# SCH_CM_Mesa_7i92TH_2024-10-26.net
KiCad netlist of a schematic drawn in EasyEDA
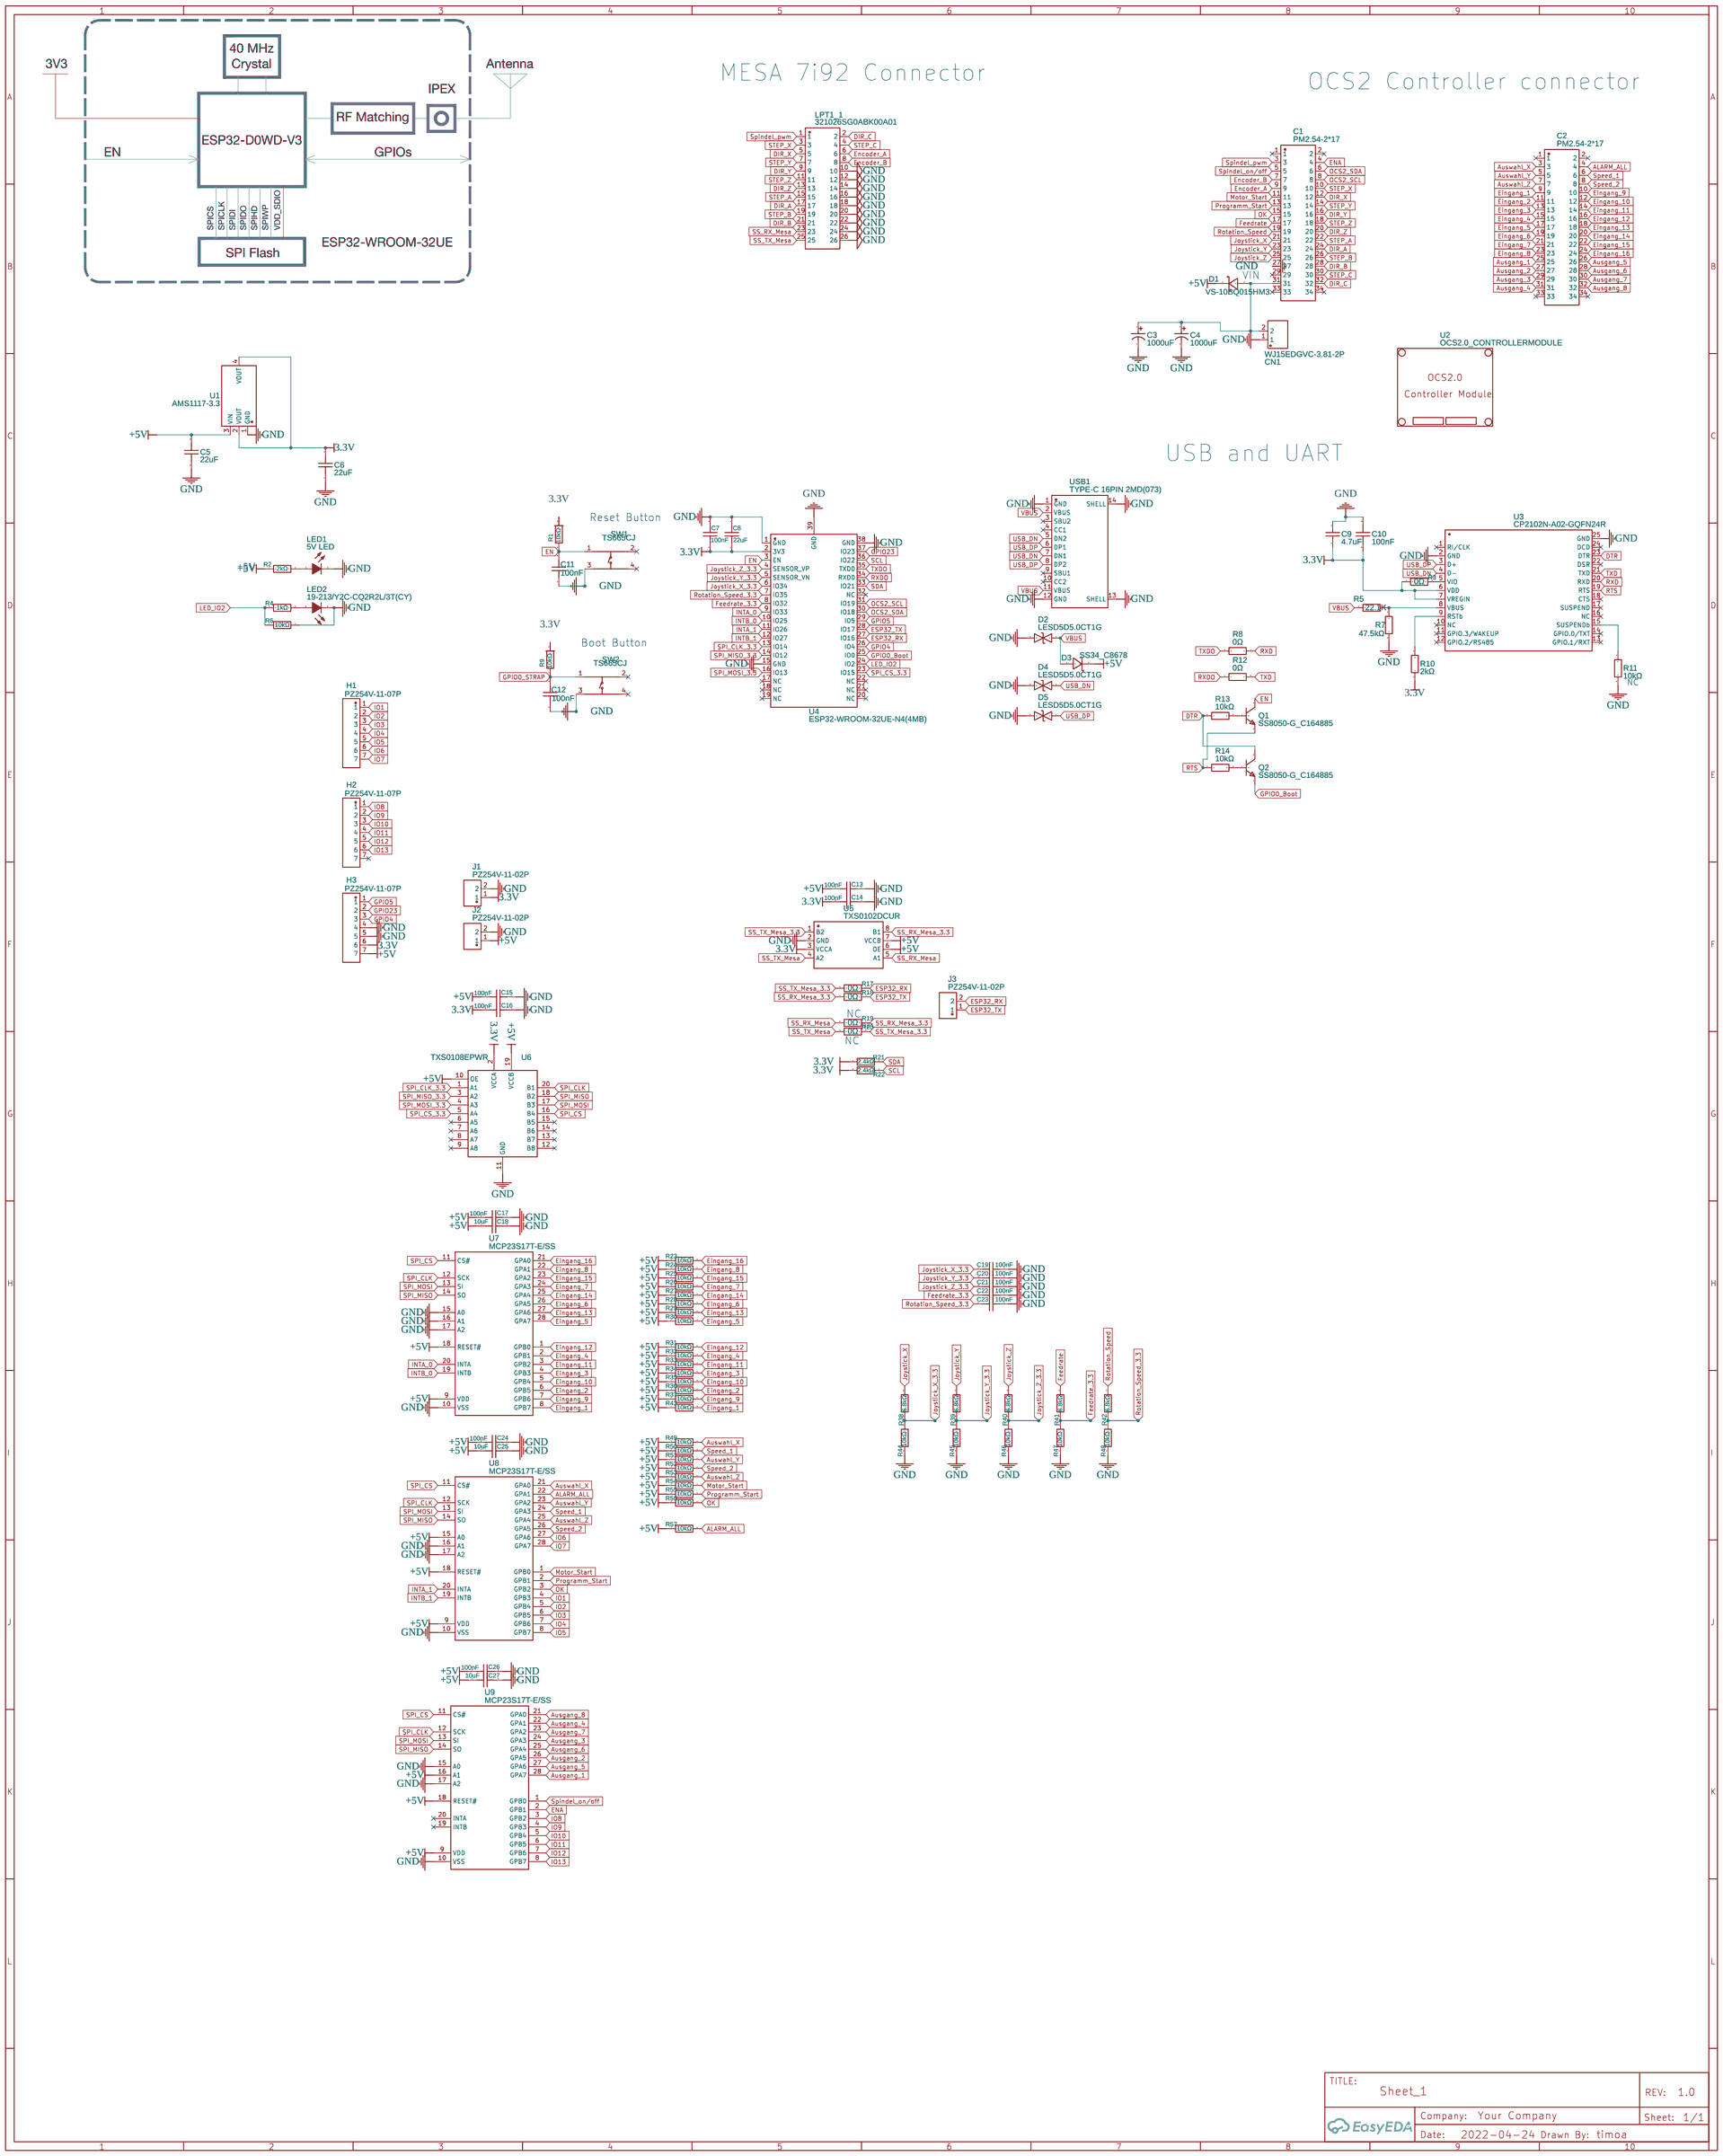
[diagram p0: schematic sheet]

(export (version "E")
  (design (tool "Eeschema 10.0.6"))
  (components
    (comp (ref "C1")
      (value "PM2.54-2*17")
      (fields (field (name "Manufacturer") "CONNFLY"))
      (libsource (lib "") (part "PM2.54-2*17"))
    )
    (comp (ref "C2")
      (value "PM2.54-2*17")
      (fields (field (name "Manufacturer") "CONNFLY"))
      (libsource (lib "") (part "PM2.54-2*17"))
    )
    (comp (ref "C3")
      (value "1000uF")
      (fields (field (name "Manufacturer Part") "RVT1C102M1010VG") (field (name "Manufacturer") "CX(承兴)"))
      (libsource (lib "") (part "UT1C102M1010VG"))
    )
    (comp (ref "C4")
      (value "1000uF")
      (fields (field (name "Manufacturer Part") "RVT1C102M1010VG") (field (name "Manufacturer") "CX(承兴)"))
      (libsource (lib "") (part "UT1C102M1010VG"))
    )
    (comp (ref "C5")
      (value "22uF")
      (fields
        (field (name "Manufacturer Part") "CC1210ZKY5V6BB226")
        (field (name "Manufacturer") "YAGEO(国巨)")
      )
      (libsource (lib "") (part "CC1210ZKY5V6BB226"))
    )
    (comp (ref "C6")
      (value "22uF")
      (fields
        (field (name "Manufacturer Part") "CC1210ZKY5V6BB226")
        (field (name "Manufacturer") "YAGEO(国巨)")
      )
      (libsource (lib "") (part "CC1210ZKY5V6BB226"))
    )
    (comp (ref "C7")
      (value "100nF")
      (fields
        (field (name "Manufacturer Part") "CC0603KRX7R9BB104")
        (field (name "Manufacturer") "YAGEO(国巨)")
      )
      (libsource (lib "") (part "CC0603KRX7R9BB104"))
    )
    (comp (ref "C8")
      (value "22uF")
      (fields
        (field (name "Manufacturer Part") "CC1210ZKY5V6BB226")
        (field (name "Manufacturer") "YAGEO(国巨)")
      )
      (libsource (lib "") (part "CC1210ZKY5V6BB226"))
    )
    (comp (ref "C9")
      (value "4.7uF")
      (fields
        (field (name "Manufacturer Part") "CL05A475MP5NRNC")
        (field (name "Manufacturer") "SAMSUNG(三星)")
      )
      (libsource (lib "") (part "CL05A475MP5NRNC"))
    )
    (comp (ref "C10")
      (value "100nF")
      (fields
        (field (name "Manufacturer Part") "CC0603KRX7R9BB104")
        (field (name "Manufacturer") "YAGEO(国巨)")
      )
      (libsource (lib "") (part "CC0603KRX7R9BB104_1"))
    )
    (comp (ref "C11")
      (value "100nF")
      (fields
        (field (name "Manufacturer Part") "CC0603KRX7R9BB104")
        (field (name "Manufacturer") "YAGEO(国巨)")
      )
      (libsource (lib "") (part "CC0603KRX7R9BB104"))
    )
    (comp (ref "C12")
      (value "100nF")
      (fields
        (field (name "Manufacturer Part") "CC0603KRX7R9BB104")
        (field (name "Manufacturer") "YAGEO(国巨)")
      )
      (libsource (lib "") (part "CC0603KRX7R9BB104"))
    )
    (comp (ref "C13")
      (value "100nF")
      (fields
        (field (name "Manufacturer Part") "CC0603KRX7R9BB104")
        (field (name "Manufacturer") "YAGEO(国巨)")
      )
      (libsource (lib "") (part "CC0603KRX7R9BB104_2"))
    )
    (comp (ref "C14")
      (value "100nF")
      (fields
        (field (name "Manufacturer Part") "CC0603KRX7R9BB104")
        (field (name "Manufacturer") "YAGEO(国巨)")
      )
      (libsource (lib "") (part "CC0603KRX7R9BB104_2"))
    )
    (comp (ref "C15")
      (value "100nF")
      (fields
        (field (name "Manufacturer Part") "CC0603KRX7R9BB104")
        (field (name "Manufacturer") "YAGEO(国巨)")
      )
      (libsource (lib "") (part "CC0603KRX7R9BB104_2"))
    )
    (comp (ref "C16")
      (value "100nF")
      (fields
        (field (name "Manufacturer Part") "CC0603KRX7R9BB104")
        (field (name "Manufacturer") "YAGEO(国巨)")
      )
      (libsource (lib "") (part "CC0603KRX7R9BB104_2"))
    )
    (comp (ref "C17")
      (value "100nF")
      (fields
        (field (name "Manufacturer Part") "CC0603KRX7R9BB104")
        (field (name "Manufacturer") "YAGEO(国巨)")
      )
      (libsource (lib "") (part "CC0603KRX7R9BB104_2"))
    )
    (comp (ref "C18")
      (value "10uF")
      (fields
        (field (name "Manufacturer Part") "CL10A106KP8NNNC")
        (field (name "Manufacturer") "SAMSUNG(三星)")
      )
      (libsource (lib "") (part "CL10A106KP8NNNC"))
    )
    (comp (ref "C19")
      (value "100nF")
      (fields
        (field (name "Manufacturer Part") "CC0603KRX7R9BB104")
        (field (name "Manufacturer") "YAGEO(国巨)")
      )
      (libsource (lib "") (part "CC0603KRX7R9BB104_2"))
    )
    (comp (ref "C20")
      (value "100nF")
      (fields
        (field (name "Manufacturer Part") "CC0603KRX7R9BB104")
        (field (name "Manufacturer") "YAGEO(国巨)")
      )
      (libsource (lib "") (part "CC0603KRX7R9BB104_2"))
    )
    (comp (ref "C21")
      (value "100nF")
      (fields
        (field (name "Manufacturer Part") "CC0603KRX7R9BB104")
        (field (name "Manufacturer") "YAGEO(国巨)")
      )
      (libsource (lib "") (part "CC0603KRX7R9BB104_2"))
    )
    (comp (ref "C22")
      (value "100nF")
      (fields
        (field (name "Manufacturer Part") "CC0603KRX7R9BB104")
        (field (name "Manufacturer") "YAGEO(国巨)")
      )
      (libsource (lib "") (part "CC0603KRX7R9BB104_2"))
    )
    (comp (ref "C23")
      (value "100nF")
      (fields
        (field (name "Manufacturer Part") "CC0603KRX7R9BB104")
        (field (name "Manufacturer") "YAGEO(国巨)")
      )
      (libsource (lib "") (part "CC0603KRX7R9BB104_2"))
    )
    (comp (ref "C24")
      (value "100nF")
      (fields
        (field (name "Manufacturer Part") "CC0603KRX7R9BB104")
        (field (name "Manufacturer") "YAGEO(国巨)")
      )
      (libsource (lib "") (part "CC0603KRX7R9BB104_2"))
    )
    (comp (ref "C25")
      (value "10uF")
      (fields
        (field (name "Manufacturer Part") "CL10A106KP8NNNC")
        (field (name "Manufacturer") "SAMSUNG(三星)")
      )
      (libsource (lib "") (part "CL10A106KP8NNNC"))
    )
    (comp (ref "C26")
      (value "100nF")
      (fields
        (field (name "Manufacturer Part") "CC0603KRX7R9BB104")
        (field (name "Manufacturer") "YAGEO(国巨)")
      )
      (libsource (lib "") (part "CC0603KRX7R9BB104_2"))
    )
    (comp (ref "C27")
      (value "10uF")
      (fields
        (field (name "Manufacturer Part") "CL10A106KP8NNNC")
        (field (name "Manufacturer") "SAMSUNG(三星)")
      )
      (libsource (lib "") (part "CL10A106KP8NNNC"))
    )
    (comp (ref "CN1")
      (value "WJ15EDGVC-3.81-2P")
      (fields (field (name "Manufacturer") "KANGNEX(康奈克斯电气)"))
      (libsource (lib "") (part "WJ15EDGVC-3.81-2P"))
    )
    (comp (ref "D1")
      (value "VS-10BQ015HM3")
      (fields
        (field (name "Manufacturer Part") "VS-10BQ015HM3/5BT")
        (field (name "Manufacturer") "Vishay Intertech")
      )
      (libsource (lib "") (part "VS-10BQ015HM3/5BT"))
    )
    (comp (ref "D2")
      (value "LESD5D5.0CT1G")
      (fields (field (name "Manufacturer") "Leshan Radio"))
      (libsource (lib "") (part "LESD5D5.0CT1G"))
    )
    (comp (ref "D3")
      (value "SS34_C8678")
      (fields (field (name "Manufacturer Part") "SS34") (field (name "Manufacturer") "MDD"))
      (libsource (lib "") (part "SS34_C8678"))
    )
    (comp (ref "D4")
      (value "LESD5D5.0CT1G")
      (fields (field (name "Manufacturer") "Leshan Radio"))
      (libsource (lib "") (part "LESD5D5.0CT1G"))
    )
    (comp (ref "D5")
      (value "LESD5D5.0CT1G")
      (fields (field (name "Manufacturer") "Leshan Radio"))
      (libsource (lib "") (part "LESD5D5.0CT1G"))
    )
    (comp (ref "H1")
      (value "PZ254V-11-07P")
      (fields (field (name "Manufacturer") "XFCN(兴飞)"))
      (libsource (lib "") (part "PZ254V-11-07P"))
    )
    (comp (ref "H2")
      (value "PZ254V-11-07P")
      (fields (field (name "Manufacturer") "XFCN(兴飞)"))
      (libsource (lib "") (part "PZ254V-11-07P"))
    )
    (comp (ref "H3")
      (value "PZ254V-11-07P")
      (fields (field (name "Manufacturer") "XFCN(兴飞)"))
      (libsource (lib "") (part "PZ254V-11-07P"))
    )
    (comp (ref "J1")
      (value "PZ254V-11-02P")
      (fields (field (name "Manufacturer") "XFCN"))
      (libsource (lib "") (part "PZ254V-11-02P"))
    )
    (comp (ref "J2")
      (value "PZ254V-11-02P")
      (fields (field (name "Manufacturer") "XFCN"))
      (libsource (lib "") (part "PZ254V-11-02P"))
    )
    (comp (ref "J3")
      (value "PZ254V-11-02P")
      (fields (field (name "Manufacturer") "XFCN"))
      (libsource (lib "") (part "PZ254V-11-02P"))
    )
    (comp (ref "LED1")
      (value "5V LED")
      (fields
        (field (name "Manufacturer Part") "19-213/Y2C-CQ2R2L/3T(CY)")
        (field (name "Manufacturer") "EVERLIGHT")
      )
      (libsource (lib "") (part "19-213/Y2C-CQ2R2L/3T(CY)"))
    )
    (comp (ref "LED2")
      (value "19-213/Y2C-CQ2R2L/3T(CY)")
      (fields (field (name "Manufacturer") "EVERLIGHT(亿光)"))
      (libsource (lib "") (part "19-213/Y2C-CQ2R2L/3T(CY)_1"))
    )
    (comp (ref "LPT1_1")
      (value "321026SG0ABK00A01")
      (fields (field (name "Manufacturer") "JILN"))
      (libsource (lib "") (part "321026SG0ABK00A01"))
    )
    (comp (ref "Q1")
      (value "SS8050-G_C164885")
      (fields (field (name "Manufacturer Part") "SS8050-G") (field (name "Manufacturer") "CJ(江苏长电/长晶)"))
      (libsource (lib "") (part "SS8050-G_C164885"))
    )
    (comp (ref "Q2")
      (value "SS8050-G_C164885")
      (fields (field (name "Manufacturer Part") "SS8050-G") (field (name "Manufacturer") "CJ(江苏长电/长晶)"))
      (libsource (lib "") (part "SS8050-G_C164885"))
    )
    (comp (ref "R1")
      (value "10kΩ")
      (fields (field (name "Manufacturer Part") "0402WGF1002TCE") (field (name "Manufacturer") "UniOhm"))
      (libsource (lib "") (part "0402WGF1002TCE_1"))
    )
    (comp (ref "R2")
      (value "2kΩ")
      (fields
        (field (name "Manufacturer Part") "0402WGF2001TCE")
        (field (name "Manufacturer") "UNI-ROYAL(厚声)")
      )
      (libsource (lib "") (part "0402WGF2001TCE"))
    )
    (comp (ref "R3")
      (value "0Ω")
      (fields
        (field (name "Manufacturer Part") "0402WGF0000TCE")
        (field (name "Manufacturer") "UNI-ROYAL(厚声)")
      )
      (libsource (lib "") (part "0402WGF0000TCE"))
    )
    (comp (ref "R4")
      (value "1kΩ")
      (fields
        (field (name "Manufacturer Part") "0402WGF1001TCE")
        (field (name "Manufacturer") "UNI-ROYAL(厚声)")
      )
      (libsource (lib "") (part "0402WGF1001TCE"))
    )
    (comp (ref "R5")
      (value "22.1K")
      (fields (field (name "Manufacturer Part") "RC0603FR-0722K1L") (field (name "Manufacturer") "YAGEO(国巨)"))
      (libsource (lib "") (part "RC0603FR-0722K1L"))
    )
    (comp (ref "R6")
      (value "10kΩ")
      (fields (field (name "Manufacturer Part") "0402WGF1002TCE") (field (name "Manufacturer") "UniOhm"))
      (libsource (lib "") (part "0402WGF1002TCE"))
    )
    (comp (ref "R7")
      (value "47.5kΩ")
      (fields (field (name "Manufacturer Part") "RTT054752FTP") (field (name "Manufacturer") "RALEC"))
      (libsource (lib "") (part "RTT054752FTP"))
    )
    (comp (ref "R8")
      (value "0Ω")
      (fields
        (field (name "Manufacturer Part") "0603WAF0000T5E")
        (field (name "Manufacturer") "UNI-ROYAL(厚声)")
      )
      (libsource (lib "") (part "0603WAF0000T5E"))
    )
    (comp (ref "R9")
      (value "10kΩ")
      (fields (field (name "Manufacturer Part") "0402WGF1002TCE") (field (name "Manufacturer") "UniOhm"))
      (libsource (lib "") (part "0402WGF1002TCE_1"))
    )
    (comp (ref "R10")
      (value "2kΩ")
      (fields
        (field (name "Manufacturer Part") "0402WGF2001TCE")
        (field (name "Manufacturer") "UNI-ROYAL(厚声)")
      )
      (libsource (lib "") (part "0402WGF2001TCE_1"))
    )
    (comp (ref "R11")
      (value "10kΩ")
      (fields
        (field (name "Manufacturer Part") "0402WGF1002TCE")
        (field (name "Manufacturer") "UNI-ROYAL(厚声)")
      )
      (libsource (lib "") (part "0402WGF1002TCE_2"))
    )
    (comp (ref "R12")
      (value "0Ω")
      (fields
        (field (name "Manufacturer Part") "0603WAF0000T5E")
        (field (name "Manufacturer") "UNI-ROYAL(厚声)")
      )
      (libsource (lib "") (part "0603WAF0000T5E"))
    )
    (comp (ref "R13")
      (value "10kΩ")
      (fields
        (field (name "Manufacturer Part") "0402WGF1002TCE")
        (field (name "Manufacturer") "UNI-ROYAL(厚声)")
      )
      (libsource (lib "") (part "0402WGF1002TCE"))
    )
    (comp (ref "R14")
      (value "10kΩ")
      (fields
        (field (name "Manufacturer Part") "0402WGF1002TCE")
        (field (name "Manufacturer") "UNI-ROYAL(厚声)")
      )
      (libsource (lib "") (part "0402WGF1002TCE"))
    )
    (comp (ref "R17")
      (value "0Ω")
      (fields
        (field (name "Manufacturer Part") "0402WGF0000TCE")
        (field (name "Manufacturer") "UNI-ROYAL(厚声)")
      )
      (libsource (lib "") (part "0402WGF0000TCE"))
    )
    (comp (ref "R18")
      (value "0Ω")
      (fields
        (field (name "Manufacturer Part") "0402WGF0000TCE")
        (field (name "Manufacturer") "UNI-ROYAL(厚声)")
      )
      (libsource (lib "") (part "0402WGF0000TCE"))
    )
    (comp (ref "R19")
      (value "0Ω")
      (fields
        (field (name "Manufacturer Part") "0402WGF0000TCE")
        (field (name "Manufacturer") "UNI-ROYAL(厚声)")
      )
      (libsource (lib "") (part "0402WGF0000TCE"))
    )
    (comp (ref "R20")
      (value "0Ω")
      (fields
        (field (name "Manufacturer Part") "0402WGF0000TCE")
        (field (name "Manufacturer") "UNI-ROYAL(厚声)")
      )
      (libsource (lib "") (part "0402WGF0000TCE"))
    )
    (comp (ref "R21")
      (value "2.4kΩ")
      (fields (field (name "Manufacturer Part") "0402WGF2401TCE") (field (name "Manufacturer") "UniOhm"))
      (libsource (lib "") (part "0402WGF2401TCE"))
    )
    (comp (ref "R22")
      (value "2.4kΩ")
      (fields (field (name "Manufacturer Part") "0402WGF2401TCE") (field (name "Manufacturer") "UniOhm"))
      (libsource (lib "") (part "0402WGF2401TCE"))
    )
    (comp (ref "R23")
      (value "10kΩ")
      (fields (field (name "Manufacturer Part") "0402WGF1002TCE") (field (name "Manufacturer") "UniOhm"))
      (libsource (lib "") (part "0402WGF1002TCE"))
    )
    (comp (ref "R24")
      (value "10kΩ")
      (fields (field (name "Manufacturer Part") "0402WGF1002TCE") (field (name "Manufacturer") "UniOhm"))
      (libsource (lib "") (part "0402WGF1002TCE"))
    )
    (comp (ref "R25")
      (value "10kΩ")
      (fields (field (name "Manufacturer Part") "0402WGF1002TCE") (field (name "Manufacturer") "UniOhm"))
      (libsource (lib "") (part "0402WGF1002TCE"))
    )
    (comp (ref "R26")
      (value "10kΩ")
      (fields (field (name "Manufacturer Part") "0402WGF1002TCE") (field (name "Manufacturer") "UniOhm"))
      (libsource (lib "") (part "0402WGF1002TCE"))
    )
    (comp (ref "R27")
      (value "10kΩ")
      (fields (field (name "Manufacturer Part") "0402WGF1002TCE") (field (name "Manufacturer") "UniOhm"))
      (libsource (lib "") (part "0402WGF1002TCE"))
    )
    (comp (ref "R28")
      (value "10kΩ")
      (fields (field (name "Manufacturer Part") "0402WGF1002TCE") (field (name "Manufacturer") "UniOhm"))
      (libsource (lib "") (part "0402WGF1002TCE"))
    )
    (comp (ref "R29")
      (value "10kΩ")
      (fields (field (name "Manufacturer Part") "0402WGF1002TCE") (field (name "Manufacturer") "UniOhm"))
      (libsource (lib "") (part "0402WGF1002TCE"))
    )
    (comp (ref "R30")
      (value "10kΩ")
      (fields (field (name "Manufacturer Part") "0402WGF1002TCE") (field (name "Manufacturer") "UniOhm"))
      (libsource (lib "") (part "0402WGF1002TCE"))
    )
    (comp (ref "R31")
      (value "10kΩ")
      (fields (field (name "Manufacturer Part") "0402WGF1002TCE") (field (name "Manufacturer") "UniOhm"))
      (libsource (lib "") (part "0402WGF1002TCE"))
    )
    (comp (ref "R32")
      (value "10kΩ")
      (fields (field (name "Manufacturer Part") "0402WGF1002TCE") (field (name "Manufacturer") "UniOhm"))
      (libsource (lib "") (part "0402WGF1002TCE"))
    )
    (comp (ref "R33")
      (value "10kΩ")
      (fields (field (name "Manufacturer Part") "0402WGF1002TCE") (field (name "Manufacturer") "UniOhm"))
      (libsource (lib "") (part "0402WGF1002TCE"))
    )
    (comp (ref "R34")
      (value "10kΩ")
      (fields (field (name "Manufacturer Part") "0402WGF1002TCE") (field (name "Manufacturer") "UniOhm"))
      (libsource (lib "") (part "0402WGF1002TCE"))
    )
    (comp (ref "R35")
      (value "10kΩ")
      (fields (field (name "Manufacturer Part") "0402WGF1002TCE") (field (name "Manufacturer") "UniOhm"))
      (libsource (lib "") (part "0402WGF1002TCE"))
    )
    (comp (ref "R36")
      (value "10kΩ")
      (fields (field (name "Manufacturer Part") "0402WGF1002TCE") (field (name "Manufacturer") "UniOhm"))
      (libsource (lib "") (part "0402WGF1002TCE"))
    )
    (comp (ref "R37")
      (value "10kΩ")
      (fields (field (name "Manufacturer Part") "0402WGF1002TCE") (field (name "Manufacturer") "UniOhm"))
      (libsource (lib "") (part "0402WGF1002TCE"))
    )
    (comp (ref "R38")
      (value "6.8kΩ")
      (fields
        (field (name "Manufacturer Part") "0805W8F6801T5E")
        (field (name "Manufacturer") "UNI-ROYAL(厚声)")
      )
      (libsource (lib "") (part "0805W8F6801T5E"))
    )
    (comp (ref "R39")
      (value "6.8kΩ")
      (fields
        (field (name "Manufacturer Part") "0805W8F6801T5E")
        (field (name "Manufacturer") "UNI-ROYAL(厚声)")
      )
      (libsource (lib "") (part "0805W8F6801T5E"))
    )
    (comp (ref "R40")
      (value "6.8kΩ")
      (fields
        (field (name "Manufacturer Part") "0805W8F6801T5E")
        (field (name "Manufacturer") "UNI-ROYAL(厚声)")
      )
      (libsource (lib "") (part "0805W8F6801T5E"))
    )
    (comp (ref "R41")
      (value "6.8kΩ")
      (fields
        (field (name "Manufacturer Part") "0805W8F6801T5E")
        (field (name "Manufacturer") "UNI-ROYAL(厚声)")
      )
      (libsource (lib "") (part "0805W8F6801T5E"))
    )
    (comp (ref "R42")
      (value "6.8kΩ")
      (fields
        (field (name "Manufacturer Part") "0805W8F6801T5E")
        (field (name "Manufacturer") "UNI-ROYAL(厚声)")
      )
      (libsource (lib "") (part "0805W8F6801T5E"))
    )
    (comp (ref "R43")
      (value "10kΩ")
      (fields (field (name "Manufacturer Part") "0402WGF1002TCE") (field (name "Manufacturer") "UniOhm"))
      (libsource (lib "") (part "0402WGF1002TCE"))
    )
    (comp (ref "R44")
      (value "10kΩ")
      (fields
        (field (name "Manufacturer Part") "0805W8F1002T5E")
        (field (name "Manufacturer") "UNI-ROYAL(厚声)")
      )
      (libsource (lib "") (part "0805W8F1002T5E"))
    )
    (comp (ref "R45")
      (value "10kΩ")
      (fields
        (field (name "Manufacturer Part") "0805W8F1002T5E")
        (field (name "Manufacturer") "UNI-ROYAL(厚声)")
      )
      (libsource (lib "") (part "0805W8F1002T5E"))
    )
    (comp (ref "R46")
      (value "10kΩ")
      (fields
        (field (name "Manufacturer Part") "0805W8F1002T5E")
        (field (name "Manufacturer") "UNI-ROYAL(厚声)")
      )
      (libsource (lib "") (part "0805W8F1002T5E"))
    )
    (comp (ref "R47")
      (value "10kΩ")
      (fields
        (field (name "Manufacturer Part") "0805W8F1002T5E")
        (field (name "Manufacturer") "UNI-ROYAL(厚声)")
      )
      (libsource (lib "") (part "0805W8F1002T5E"))
    )
    (comp (ref "R48")
      (value "10kΩ")
      (fields
        (field (name "Manufacturer Part") "0805W8F1002T5E")
        (field (name "Manufacturer") "UNI-ROYAL(厚声)")
      )
      (libsource (lib "") (part "0805W8F1002T5E"))
    )
    (comp (ref "R49")
      (value "10kΩ")
      (fields (field (name "Manufacturer Part") "0402WGF1002TCE") (field (name "Manufacturer") "UniOhm"))
      (libsource (lib "") (part "0402WGF1002TCE"))
    )
    (comp (ref "R50")
      (value "10kΩ")
      (fields (field (name "Manufacturer Part") "0402WGF1002TCE") (field (name "Manufacturer") "UniOhm"))
      (libsource (lib "") (part "0402WGF1002TCE"))
    )
    (comp (ref "R51")
      (value "10kΩ")
      (fields (field (name "Manufacturer Part") "0402WGF1002TCE") (field (name "Manufacturer") "UniOhm"))
      (libsource (lib "") (part "0402WGF1002TCE"))
    )
    (comp (ref "R52")
      (value "10kΩ")
      (fields (field (name "Manufacturer Part") "0402WGF1002TCE") (field (name "Manufacturer") "UniOhm"))
      (libsource (lib "") (part "0402WGF1002TCE"))
    )
    (comp (ref "R53")
      (value "10kΩ")
      (fields (field (name "Manufacturer Part") "0402WGF1002TCE") (field (name "Manufacturer") "UniOhm"))
      (libsource (lib "") (part "0402WGF1002TCE"))
    )
    (comp (ref "R54")
      (value "10kΩ")
      (fields (field (name "Manufacturer Part") "0402WGF1002TCE") (field (name "Manufacturer") "UniOhm"))
      (libsource (lib "") (part "0402WGF1002TCE"))
    )
    (comp (ref "R55")
      (value "10kΩ")
      (fields (field (name "Manufacturer Part") "0402WGF1002TCE") (field (name "Manufacturer") "UniOhm"))
      (libsource (lib "") (part "0402WGF1002TCE"))
    )
    (comp (ref "R56")
      (value "10kΩ")
      (fields (field (name "Manufacturer Part") "0402WGF1002TCE") (field (name "Manufacturer") "UniOhm"))
      (libsource (lib "") (part "0402WGF1002TCE"))
    )
    (comp (ref "R57")
      (value "10kΩ")
      (fields (field (name "Manufacturer Part") "0402WGF1002TCE") (field (name "Manufacturer") "UniOhm"))
      (libsource (lib "") (part "0402WGF1002TCE"))
    )
    (comp (ref "SW1")
      (value "TS665CJ")
      (fields (field (name "Manufacturer") "SHOU HAN"))
      (libsource (lib "") (part "TS665CJ"))
    )
    (comp (ref "SW2")
      (value "TS665CJ")
      (fields (field (name "Manufacturer") "SHOU HAN"))
      (libsource (lib "") (part "TS665CJ"))
    )
    (comp (ref "U1")
      (value "AMS1117-3.3")
      (fields (field (name "Manufacturer") "AMS"))
      (libsource (lib "") (part "AMS1117-3.3"))
    )
    (comp (ref "U2")
      (value "OCS2.0_CONTROLLERMODULE")
      (fields (field (name "Manufacturer") "timo"))
      (libsource (lib "") (part "OCS2.0_CONTROLLERMODULE"))
    )
    (comp (ref "U3")
      (value "CP2102N-A02-GQFN24R")
      (fields (field (name "Manufacturer") "SILICON LABS(芯科)"))
      (libsource (lib "") (part "CP2102N-A02-GQFN24R"))
    )
    (comp (ref "U4")
      (value "ESP32-WROOM-32UE-N4(4MB)")
      (fields
        (field (name "Manufacturer Part") "ESP32-WROOM-32UE-N4")
        (field (name "Manufacturer") "ESPRESSIF(乐鑫)")
      )
      (libsource (lib "") (part "ESP32-WROOM-32UE(4MB)"))
    )
    (comp (ref "U5")
      (value "TXS0102DCUR")
      (fields (field (name "Manufacturer") "TI(德州仪器)"))
      (libsource (lib "") (part "TXS0102DCUR"))
    )
    (comp (ref "U6")
      (value "TXS0108EPWR")
      (fields (field (name "Manufacturer") "TI(德州仪器)"))
      (libsource (lib "") (part "TXS0108EPWR"))
    )
    (comp (ref "U7")
      (value "MCP23S17T-E/SS")
      (fields (field (name "Manufacturer") "MICROCHIP(美国微芯)"))
      (libsource (lib "") (part "MCP23S17T-E/SS"))
    )
    (comp (ref "U8")
      (value "MCP23S17T-E/SS")
      (fields (field (name "Manufacturer") "MICROCHIP(美国微芯)"))
      (libsource (lib "") (part "MCP23S17T-E/SS"))
    )
    (comp (ref "U9")
      (value "MCP23S17T-E/SS")
      (fields (field (name "Manufacturer") "MICROCHIP(美国微芯)"))
      (libsource (lib "") (part "MCP23S17T-E/SS"))
    )
    (comp (ref "USB1")
      (value "TYPE-C 16PIN 2MD(073)")
      (fields (field (name "Manufacturer") "SHOU HAN(首韩)"))
      (libsource (lib "") (part "TYPE-C 16PIN 2MD(073)"))
    )
  )
  (nets
    (net (code "1") (name "+5V") (class "Default")
      (node (ref "C13") (pin "2") (pinfunction "2_2") (pintype "unspecified"))
      (node (ref "C15") (pin "2") (pinfunction "2_2") (pintype "unspecified"))
      (node (ref "C17") (pin "2") (pinfunction "2_2") (pintype "unspecified"))
      (node (ref "C18") (pin "1") (pinfunction "1_1") (pintype "unspecified"))
      (node (ref "C24") (pin "2") (pinfunction "2_2") (pintype "unspecified"))
      (node (ref "C25") (pin "1") (pinfunction "1_1") (pintype "unspecified"))
      (node (ref "C26") (pin "2") (pinfunction "2_2") (pintype "unspecified"))
      (node (ref "C27") (pin "1") (pinfunction "1_1") (pintype "unspecified"))
      (node (ref "C5") (pin "2") (pinfunction "2_2") (pintype "unspecified"))
      (node (ref "D1") (pin "1") (pinfunction "C_1") (pintype "unspecified"))
      (node (ref "D3") (pin "1") (pinfunction "K_1") (pintype "unspecified"))
      (node (ref "H3") (pin "7") (pinfunction "7_7") (pintype "unspecified"))
      (node (ref "J2") (pin "1") (pinfunction "1_1") (pintype "unspecified"))
      (node (ref "R2") (pin "1") (pinfunction "1_1") (pintype "input"))
      (node (ref "R23") (pin "1") (pinfunction "1_1") (pintype "input"))
      (node (ref "R24") (pin "1") (pinfunction "1_1") (pintype "input"))
      (node (ref "R25") (pin "1") (pinfunction "1_1") (pintype "input"))
      (node (ref "R26") (pin "1") (pinfunction "1_1") (pintype "input"))
      (node (ref "R27") (pin "1") (pinfunction "1_1") (pintype "input"))
      (node (ref "R28") (pin "1") (pinfunction "1_1") (pintype "input"))
      (node (ref "R29") (pin "1") (pinfunction "1_1") (pintype "input"))
      (node (ref "R30") (pin "1") (pinfunction "1_1") (pintype "input"))
      (node (ref "R31") (pin "1") (pinfunction "1_1") (pintype "input"))
      (node (ref "R32") (pin "1") (pinfunction "1_1") (pintype "input"))
      (node (ref "R33") (pin "1") (pinfunction "1_1") (pintype "input"))
      (node (ref "R34") (pin "1") (pinfunction "1_1") (pintype "input"))
      (node (ref "R35") (pin "1") (pinfunction "1_1") (pintype "input"))
      (node (ref "R36") (pin "1") (pinfunction "1_1") (pintype "input"))
      (node (ref "R37") (pin "1") (pinfunction "1_1") (pintype "input"))
      (node (ref "R43") (pin "1") (pinfunction "1_1") (pintype "input"))
      (node (ref "R49") (pin "1") (pinfunction "1_1") (pintype "input"))
      (node (ref "R50") (pin "1") (pinfunction "1_1") (pintype "input"))
      (node (ref "R51") (pin "1") (pinfunction "1_1") (pintype "input"))
      (node (ref "R52") (pin "1") (pinfunction "1_1") (pintype "input"))
      (node (ref "R53") (pin "1") (pinfunction "1_1") (pintype "input"))
      (node (ref "R54") (pin "1") (pinfunction "1_1") (pintype "input"))
      (node (ref "R55") (pin "1") (pinfunction "1_1") (pintype "input"))
      (node (ref "R56") (pin "1") (pinfunction "1_1") (pintype "input"))
      (node (ref "R57") (pin "1") (pinfunction "1_1") (pintype "input"))
      (node (ref "U1") (pin "3") (pinfunction "VIN_3") (pintype "unspecified"))
      (node (ref "U5") (pin "6") (pinfunction "OE_6") (pintype "unspecified"))
      (node (ref "U5") (pin "7") (pinfunction "VCCB_7") (pintype "unspecified"))
      (node (ref "U6") (pin "10") (pinfunction "OE_10") (pintype "unspecified"))
      (node (ref "U6") (pin "19") (pinfunction "VCCB_19") (pintype "unspecified"))
      (node (ref "U7") (pin "18") (pinfunction "RESET#_18") (pintype "unspecified"))
      (node (ref "U7") (pin "9") (pinfunction "VDD_9") (pintype "passive"))
      (node (ref "U8") (pin "15") (pinfunction "A0_15") (pintype "unspecified"))
      (node (ref "U8") (pin "18") (pinfunction "RESET#_18") (pintype "unspecified"))
      (node (ref "U8") (pin "9") (pinfunction "VDD_9") (pintype "passive"))
      (node (ref "U9") (pin "16") (pinfunction "A1_16") (pintype "unspecified"))
      (node (ref "U9") (pin "18") (pinfunction "RESET#_18") (pintype "unspecified"))
      (node (ref "U9") (pin "9") (pinfunction "VDD_9") (pintype "passive"))
    )
    (net (code "2") (name "3.3V") (class "Default")
      (node (ref "C10") (pin "1") (pinfunction "1_1") (pintype "unspecified"))
      (node (ref "C14") (pin "2") (pinfunction "2_2") (pintype "unspecified"))
      (node (ref "C16") (pin "2") (pinfunction "2_2") (pintype "unspecified"))
      (node (ref "C6") (pin "2") (pinfunction "2_2") (pintype "unspecified"))
      (node (ref "C7") (pin "1") (pinfunction "1_1") (pintype "unspecified"))
      (node (ref "C8") (pin "1") (pinfunction "1_1") (pintype "unspecified"))
      (node (ref "C9") (pin "1") (pinfunction "1_1") (pintype "input"))
      (node (ref "H3") (pin "6") (pinfunction "6_6") (pintype "unspecified"))
      (node (ref "J1") (pin "1") (pinfunction "1_1") (pintype "unspecified"))
      (node (ref "R1") (pin "2") (pinfunction "2_2") (pintype "input"))
      (node (ref "R10") (pin "1") (pinfunction "1_1") (pintype "input"))
      (node (ref "R21") (pin "2") (pinfunction "2_2") (pintype "input"))
      (node (ref "R22") (pin "2") (pinfunction "2_2") (pintype "input"))
      (node (ref "R3") (pin "2") (pinfunction "2_2") (pintype "input"))
      (node (ref "R9") (pin "2") (pinfunction "2_2") (pintype "input"))
      (node (ref "U1") (pin "2") (pinfunction "VOUT_2") (pintype "unspecified"))
      (node (ref "U1") (pin "4") (pinfunction "VOUT_4") (pintype "unspecified"))
      (node (ref "U3") (pin "6") (pinfunction "VDD_6") (pintype "unspecified"))
      (node (ref "U3") (pin "7") (pinfunction "VREGIN_7") (pintype "unspecified"))
      (node (ref "U4") (pin "2") (pinfunction "3V3_2") (pintype "unspecified"))
      (node (ref "U5") (pin "3") (pinfunction "VCCA_3") (pintype "unspecified"))
      (node (ref "U6") (pin "2") (pinfunction "VCCA_2") (pintype "unspecified"))
    )
    (net (code "3") (name "ALARM_ALL") (class "Default")
      (node (ref "C2") (pin "4") (pinfunction "4_4") (pintype "unspecified"))
      (node (ref "R57") (pin "2") (pinfunction "2_2") (pintype "input"))
      (node (ref "U8") (pin "22") (pinfunction "GPA1_22") (pintype "bidirectional"))
    )
    (net (code "4") (name "Ausgang_1") (class "Default")
      (node (ref "C2") (pin "25") (pinfunction "25_25") (pintype "unspecified"))
      (node (ref "U9") (pin "28") (pinfunction "GPA7_28") (pintype "bidirectional"))
    )
    (net (code "5") (name "Ausgang_2") (class "Default")
      (node (ref "C2") (pin "27") (pinfunction "27_27") (pintype "unspecified"))
      (node (ref "U9") (pin "26") (pinfunction "GPA5_26") (pintype "bidirectional"))
    )
    (net (code "6") (name "Ausgang_3") (class "Default")
      (node (ref "C2") (pin "29") (pinfunction "29_29") (pintype "unspecified"))
      (node (ref "U9") (pin "24") (pinfunction "GPA3_24") (pintype "bidirectional"))
    )
    (net (code "7") (name "Ausgang_4") (class "Default")
      (node (ref "C2") (pin "31") (pinfunction "31_31") (pintype "unspecified"))
      (node (ref "U9") (pin "22") (pinfunction "GPA1_22") (pintype "bidirectional"))
    )
    (net (code "8") (name "Ausgang_5") (class "Default")
      (node (ref "C2") (pin "26") (pinfunction "26_26") (pintype "unspecified"))
      (node (ref "U9") (pin "27") (pinfunction "GPA6_27") (pintype "bidirectional"))
    )
    (net (code "9") (name "Ausgang_6") (class "Default")
      (node (ref "C2") (pin "28") (pinfunction "28_28") (pintype "unspecified"))
      (node (ref "U9") (pin "25") (pinfunction "GPA4_25") (pintype "bidirectional"))
    )
    (net (code "10") (name "Ausgang_7") (class "Default")
      (node (ref "C2") (pin "30") (pinfunction "30_30") (pintype "unspecified"))
      (node (ref "U9") (pin "23") (pinfunction "GPA2_23") (pintype "bidirectional"))
    )
    (net (code "11") (name "Ausgang_8") (class "Default")
      (node (ref "C2") (pin "32") (pinfunction "32_32") (pintype "unspecified"))
      (node (ref "U9") (pin "21") (pinfunction "GPA0_21") (pintype "bidirectional"))
    )
    (net (code "12") (name "Auswahl_X") (class "Default")
      (node (ref "C2") (pin "3") (pinfunction "3_3") (pintype "unspecified"))
      (node (ref "R49") (pin "2") (pinfunction "2_2") (pintype "input"))
      (node (ref "U8") (pin "21") (pinfunction "GPA0_21") (pintype "bidirectional"))
    )
    (net (code "13") (name "Auswahl_Y") (class "Default")
      (node (ref "C2") (pin "5") (pinfunction "5_5") (pintype "unspecified"))
      (node (ref "R51") (pin "2") (pinfunction "2_2") (pintype "input"))
      (node (ref "U8") (pin "23") (pinfunction "GPA2_23") (pintype "bidirectional"))
    )
    (net (code "14") (name "Auswahl_Z") (class "Default")
      (node (ref "C2") (pin "7") (pinfunction "7_7") (pintype "unspecified"))
      (node (ref "R53") (pin "2") (pinfunction "2_2") (pintype "input"))
      (node (ref "U8") (pin "25") (pinfunction "GPA4_25") (pintype "bidirectional"))
    )
    (net (code "15") (name "DIR_A") (class "Default")
      (node (ref "C1") (pin "24") (pinfunction "24_24") (pintype "unspecified"))
      (node (ref "LPT1_1") (pin "17") (pinfunction "17_17") (pintype "unspecified"))
    )
    (net (code "16") (name "DIR_B") (class "Default")
      (node (ref "C1") (pin "28") (pinfunction "28_28") (pintype "unspecified"))
      (node (ref "LPT1_1") (pin "21") (pinfunction "21_21") (pintype "unspecified"))
    )
    (net (code "17") (name "DIR_C") (class "Default")
      (node (ref "C1") (pin "32") (pinfunction "32_32") (pintype "unspecified"))
      (node (ref "LPT1_1") (pin "2") (pinfunction "2_2") (pintype "unspecified"))
    )
    (net (code "18") (name "DIR_X") (class "Default")
      (node (ref "C1") (pin "12") (pinfunction "12_12") (pintype "unspecified"))
      (node (ref "LPT1_1") (pin "5") (pinfunction "5_5") (pintype "unspecified"))
    )
    (net (code "19") (name "DIR_Y") (class "Default")
      (node (ref "C1") (pin "16") (pinfunction "16_16") (pintype "unspecified"))
      (node (ref "LPT1_1") (pin "9") (pinfunction "9_9") (pintype "unspecified"))
    )
    (net (code "20") (name "DIR_Z") (class "Default")
      (node (ref "C1") (pin "20") (pinfunction "20_20") (pintype "unspecified"))
      (node (ref "LPT1_1") (pin "13") (pinfunction "13_13") (pintype "unspecified"))
    )
    (net (code "21") (name "DTR") (class "Default")
      (node (ref "Q2") (pin "3") (pinfunction "C_3") (pintype "unspecified"))
      (node (ref "R13") (pin "1") (pinfunction "1_1") (pintype "input"))
      (node (ref "U3") (pin "23") (pinfunction "DTR_23") (pintype "unspecified"))
    )
    (net (code "22") (name "EN") (class "Default")
      (node (ref "C11") (pin "2") (pinfunction "2_2") (pintype "unspecified"))
      (node (ref "Q1") (pin "3") (pinfunction "C_3") (pintype "unspecified"))
      (node (ref "R1") (pin "1") (pinfunction "1_1") (pintype "input"))
      (node (ref "SW1") (pin "1") (pinfunction "A_1") (pintype "unspecified"))
      (node (ref "U4") (pin "3") (pinfunction "EN_3") (pintype "unspecified"))
    )
    (net (code "23") (name "ENA") (class "Default")
      (node (ref "C1") (pin "4") (pinfunction "4_4") (pintype "unspecified"))
      (node (ref "U9") (pin "2") (pinfunction "GPB1_2") (pintype "bidirectional"))
    )
    (net (code "24") (name "ESP32_RX") (class "Default")
      (node (ref "J3") (pin "2") (pinfunction "2_2") (pintype "unspecified"))
      (node (ref "R17") (pin "1") (pinfunction "1_1") (pintype "input"))
      (node (ref "U4") (pin "27") (pinfunction "IO16_27") (pintype "unspecified"))
    )
    (net (code "25") (name "ESP32_TX") (class "Default")
      (node (ref "J3") (pin "1") (pinfunction "1_1") (pintype "unspecified"))
      (node (ref "R18") (pin "1") (pinfunction "1_1") (pintype "input"))
      (node (ref "U4") (pin "28") (pinfunction "IO17_28") (pintype "unspecified"))
    )
    (net (code "26") (name "Eingang_1") (class "Default")
      (node (ref "C2") (pin "9") (pinfunction "9_9") (pintype "unspecified"))
      (node (ref "R43") (pin "2") (pinfunction "2_2") (pintype "input"))
      (node (ref "U7") (pin "8") (pinfunction "GPB7_8") (pintype "bidirectional"))
    )
    (net (code "27") (name "Eingang_2") (class "Default")
      (node (ref "C2") (pin "11") (pinfunction "11_11") (pintype "unspecified"))
      (node (ref "R36") (pin "2") (pinfunction "2_2") (pintype "input"))
      (node (ref "U7") (pin "6") (pinfunction "GPB5_6") (pintype "bidirectional"))
    )
    (net (code "28") (name "Eingang_3") (class "Default")
      (node (ref "C2") (pin "13") (pinfunction "13_13") (pintype "unspecified"))
      (node (ref "R34") (pin "2") (pinfunction "2_2") (pintype "input"))
      (node (ref "U7") (pin "4") (pinfunction "GPB3_4") (pintype "bidirectional"))
    )
    (net (code "29") (name "Eingang_4") (class "Default")
      (node (ref "C2") (pin "15") (pinfunction "15_15") (pintype "unspecified"))
      (node (ref "R32") (pin "2") (pinfunction "2_2") (pintype "input"))
      (node (ref "U7") (pin "2") (pinfunction "GPB1_2") (pintype "bidirectional"))
    )
    (net (code "30") (name "Eingang_5") (class "Default")
      (node (ref "C2") (pin "17") (pinfunction "17_17") (pintype "unspecified"))
      (node (ref "R30") (pin "2") (pinfunction "2_2") (pintype "input"))
      (node (ref "U7") (pin "28") (pinfunction "GPA7_28") (pintype "bidirectional"))
    )
    (net (code "31") (name "Eingang_6") (class "Default")
      (node (ref "C2") (pin "19") (pinfunction "19_19") (pintype "unspecified"))
      (node (ref "R28") (pin "2") (pinfunction "2_2") (pintype "input"))
      (node (ref "U7") (pin "26") (pinfunction "GPA5_26") (pintype "bidirectional"))
    )
    (net (code "32") (name "Eingang_7") (class "Default")
      (node (ref "C2") (pin "21") (pinfunction "21_21") (pintype "unspecified"))
      (node (ref "R26") (pin "2") (pinfunction "2_2") (pintype "input"))
      (node (ref "U7") (pin "24") (pinfunction "GPA3_24") (pintype "bidirectional"))
    )
    (net (code "33") (name "Eingang_8") (class "Default")
      (node (ref "C2") (pin "23") (pinfunction "23_23") (pintype "unspecified"))
      (node (ref "R24") (pin "2") (pinfunction "2_2") (pintype "input"))
      (node (ref "U7") (pin "22") (pinfunction "GPA1_22") (pintype "bidirectional"))
    )
    (net (code "34") (name "Eingang_9") (class "Default")
      (node (ref "C2") (pin "10") (pinfunction "10_10") (pintype "unspecified"))
      (node (ref "R37") (pin "2") (pinfunction "2_2") (pintype "input"))
      (node (ref "U7") (pin "7") (pinfunction "GPB6_7") (pintype "bidirectional"))
    )
    (net (code "35") (name "Eingang_10") (class "Default")
      (node (ref "C2") (pin "12") (pinfunction "12_12") (pintype "unspecified"))
      (node (ref "R35") (pin "2") (pinfunction "2_2") (pintype "input"))
      (node (ref "U7") (pin "5") (pinfunction "GPB4_5") (pintype "bidirectional"))
    )
    (net (code "36") (name "Eingang_11") (class "Default")
      (node (ref "C2") (pin "14") (pinfunction "14_14") (pintype "unspecified"))
      (node (ref "R33") (pin "2") (pinfunction "2_2") (pintype "input"))
      (node (ref "U7") (pin "3") (pinfunction "GPB2_3") (pintype "bidirectional"))
    )
    (net (code "37") (name "Eingang_12") (class "Default")
      (node (ref "C2") (pin "16") (pinfunction "16_16") (pintype "unspecified"))
      (node (ref "R31") (pin "2") (pinfunction "2_2") (pintype "input"))
      (node (ref "U7") (pin "1") (pinfunction "GPB0_1") (pintype "bidirectional"))
    )
    (net (code "38") (name "Eingang_13") (class "Default")
      (node (ref "C2") (pin "18") (pinfunction "18_18") (pintype "unspecified"))
      (node (ref "R29") (pin "2") (pinfunction "2_2") (pintype "input"))
      (node (ref "U7") (pin "27") (pinfunction "GPA6_27") (pintype "bidirectional"))
    )
    (net (code "39") (name "Eingang_14") (class "Default")
      (node (ref "C2") (pin "20") (pinfunction "20_20") (pintype "unspecified"))
      (node (ref "R27") (pin "2") (pinfunction "2_2") (pintype "input"))
      (node (ref "U7") (pin "25") (pinfunction "GPA4_25") (pintype "bidirectional"))
    )
    (net (code "40") (name "Eingang_15") (class "Default")
      (node (ref "C2") (pin "22") (pinfunction "22_22") (pintype "unspecified"))
      (node (ref "R25") (pin "2") (pinfunction "2_2") (pintype "input"))
      (node (ref "U7") (pin "23") (pinfunction "GPA2_23") (pintype "bidirectional"))
    )
    (net (code "41") (name "Eingang_16") (class "Default")
      (node (ref "C2") (pin "24") (pinfunction "24_24") (pintype "unspecified"))
      (node (ref "R23") (pin "2") (pinfunction "2_2") (pintype "input"))
      (node (ref "U7") (pin "21") (pinfunction "GPA0_21") (pintype "bidirectional"))
    )
    (net (code "42") (name "Encoder_A") (class "Default")
      (node (ref "C1") (pin "9") (pinfunction "9_9") (pintype "unspecified"))
      (node (ref "LPT1_1") (pin "6") (pinfunction "6_6") (pintype "unspecified"))
    )
    (net (code "43") (name "Encoder_B") (class "Default")
      (node (ref "C1") (pin "7") (pinfunction "7_7") (pintype "unspecified"))
      (node (ref "LPT1_1") (pin "8") (pinfunction "8_8") (pintype "unspecified"))
    )
    (net (code "44") (name "Feedrate") (class "Default")
      (node (ref "C1") (pin "17") (pinfunction "17_17") (pintype "unspecified"))
      (node (ref "R41") (pin "2") (pinfunction "2_2") (pintype "input"))
    )
    (net (code "45") (name "Feedrate_3.3") (class "Default")
      (node (ref "C22") (pin "2") (pinfunction "2_2") (pintype "unspecified"))
      (node (ref "R41") (pin "1") (pinfunction "1_1") (pintype "input"))
      (node (ref "R47") (pin "2") (pinfunction "2_2") (pintype "input"))
      (node (ref "U4") (pin "8") (pinfunction "IO32_8") (pintype "unspecified"))
    )
    (net (code "46") (name "GND") (class "Default")
      (node (ref "C1") (pin "27") (pinfunction "27_27") (pintype "unspecified"))
      (node (ref "C10") (pin "2") (pinfunction "2_2") (pintype "unspecified"))
      (node (ref "C11") (pin "1") (pinfunction "1_1") (pintype "unspecified"))
      (node (ref "C12") (pin "1") (pinfunction "1_1") (pintype "unspecified"))
      (node (ref "C13") (pin "1") (pinfunction "1_1") (pintype "unspecified"))
      (node (ref "C14") (pin "1") (pinfunction "1_1") (pintype "unspecified"))
      (node (ref "C15") (pin "1") (pinfunction "1_1") (pintype "unspecified"))
      (node (ref "C16") (pin "1") (pinfunction "1_1") (pintype "unspecified"))
      (node (ref "C17") (pin "1") (pinfunction "1_1") (pintype "unspecified"))
      (node (ref "C18") (pin "2") (pinfunction "2_2") (pintype "unspecified"))
      (node (ref "C19") (pin "1") (pinfunction "1_1") (pintype "unspecified"))
      (node (ref "C20") (pin "1") (pinfunction "1_1") (pintype "unspecified"))
      (node (ref "C21") (pin "1") (pinfunction "1_1") (pintype "unspecified"))
      (node (ref "C22") (pin "1") (pinfunction "1_1") (pintype "unspecified"))
      (node (ref "C23") (pin "1") (pinfunction "1_1") (pintype "unspecified"))
      (node (ref "C24") (pin "1") (pinfunction "1_1") (pintype "unspecified"))
      (node (ref "C25") (pin "2") (pinfunction "2_2") (pintype "unspecified"))
      (node (ref "C26") (pin "1") (pinfunction "1_1") (pintype "unspecified"))
      (node (ref "C27") (pin "2") (pinfunction "2_2") (pintype "unspecified"))
      (node (ref "C3") (pin "2") (pinfunction "2_2") (pintype "input"))
      (node (ref "C4") (pin "2") (pinfunction "2_2") (pintype "input"))
      (node (ref "C5") (pin "1") (pinfunction "1_1") (pintype "unspecified"))
      (node (ref "C6") (pin "1") (pinfunction "1_1") (pintype "unspecified"))
      (node (ref "C7") (pin "2") (pinfunction "2_2") (pintype "unspecified"))
      (node (ref "C8") (pin "2") (pinfunction "2_2") (pintype "unspecified"))
      (node (ref "C9") (pin "2") (pinfunction "2_2") (pintype "input"))
      (node (ref "CN1") (pin "1") (pinfunction "1_1") (pintype "unspecified"))
      (node (ref "D2") (pin "2") (pinfunction "2_2") (pintype "unspecified"))
      (node (ref "D4") (pin "2") (pinfunction "2_2") (pintype "unspecified"))
      (node (ref "D5") (pin "2") (pinfunction "2_2") (pintype "unspecified"))
      (node (ref "H3") (pin "4") (pinfunction "4_4") (pintype "unspecified"))
      (node (ref "H3") (pin "5") (pinfunction "5_5") (pintype "unspecified"))
      (node (ref "J1") (pin "2") (pinfunction "2_2") (pintype "unspecified"))
      (node (ref "J2") (pin "2") (pinfunction "2_2") (pintype "unspecified"))
      (node (ref "LED1") (pin "2") (pinfunction "C_2") (pintype "input"))
      (node (ref "LED2") (pin "1") (pinfunction "C_1") (pintype "input"))
      (node (ref "LPT1_1") (pin "10") (pinfunction "10_10") (pintype "unspecified"))
      (node (ref "LPT1_1") (pin "12") (pinfunction "12_12") (pintype "unspecified"))
      (node (ref "LPT1_1") (pin "14") (pinfunction "14_14") (pintype "unspecified"))
      (node (ref "LPT1_1") (pin "16") (pinfunction "16_16") (pintype "unspecified"))
      (node (ref "LPT1_1") (pin "18") (pinfunction "18_18") (pintype "unspecified"))
      (node (ref "LPT1_1") (pin "20") (pinfunction "20_20") (pintype "unspecified"))
      (node (ref "LPT1_1") (pin "22") (pinfunction "22_22") (pintype "unspecified"))
      (node (ref "LPT1_1") (pin "24") (pinfunction "24_24") (pintype "unspecified"))
      (node (ref "LPT1_1") (pin "26") (pinfunction "26_26") (pintype "unspecified"))
      (node (ref "R11") (pin "2") (pinfunction "2_2") (pintype "input"))
      (node (ref "R44") (pin "1") (pinfunction "1_1") (pintype "input"))
      (node (ref "R45") (pin "1") (pinfunction "1_1") (pintype "input"))
      (node (ref "R46") (pin "1") (pinfunction "1_1") (pintype "input"))
      (node (ref "R47") (pin "1") (pinfunction "1_1") (pintype "input"))
      (node (ref "R48") (pin "1") (pinfunction "1_1") (pintype "input"))
      (node (ref "R6") (pin "2") (pinfunction "2_2") (pintype "input"))
      (node (ref "R7") (pin "1") (pinfunction "1_1") (pintype "unspecified"))
      (node (ref "SW1") (pin "3") (pinfunction "C_3") (pintype "unspecified"))
      (node (ref "SW2") (pin "3") (pinfunction "C_3") (pintype "unspecified"))
      (node (ref "U1") (pin "1") (pinfunction "GND_1") (pintype "unspecified"))
      (node (ref "U3") (pin "2") (pinfunction "GND_2") (pintype "unspecified"))
      (node (ref "U3") (pin "25") (pinfunction "GND_25") (pintype "unspecified"))
      (node (ref "U4") (pin "1") (pinfunction "GND_1") (pintype "unspecified"))
      (node (ref "U4") (pin "15") (pinfunction "GND_15") (pintype "unspecified"))
      (node (ref "U4") (pin "38") (pinfunction "GND_38") (pintype "unspecified"))
      (node (ref "U4") (pin "39") (pinfunction "GND_39") (pintype "unspecified"))
      (node (ref "U5") (pin "2") (pinfunction "GND_2") (pintype "unspecified"))
      (node (ref "U6") (pin "11") (pinfunction "GND_11") (pintype "unspecified"))
      (node (ref "U7") (pin "10") (pinfunction "VSS_10") (pintype "passive"))
      (node (ref "U7") (pin "15") (pinfunction "A0_15") (pintype "unspecified"))
      (node (ref "U7") (pin "16") (pinfunction "A1_16") (pintype "unspecified"))
      (node (ref "U7") (pin "17") (pinfunction "A2_17") (pintype "unspecified"))
      (node (ref "U8") (pin "10") (pinfunction "VSS_10") (pintype "passive"))
      (node (ref "U8") (pin "16") (pinfunction "A1_16") (pintype "unspecified"))
      (node (ref "U8") (pin "17") (pinfunction "A2_17") (pintype "unspecified"))
      (node (ref "U9") (pin "10") (pinfunction "VSS_10") (pintype "passive"))
      (node (ref "U9") (pin "15") (pinfunction "A0_15") (pintype "unspecified"))
      (node (ref "U9") (pin "17") (pinfunction "A2_17") (pintype "unspecified"))
      (node (ref "USB1") (pin "1") (pinfunction "GND_1") (pintype "unspecified"))
      (node (ref "USB1") (pin "12") (pinfunction "GND_12") (pintype "unspecified"))
      (node (ref "USB1") (pin "13") (pinfunction "SHELL_13") (pintype "unspecified"))
      (node (ref "USB1") (pin "14") (pinfunction "SHELL_14") (pintype "unspecified"))
    )
    (net (code "47") (name "GPIO0_Boot") (class "Default")
      (node (ref "Q2") (pin "2") (pinfunction "E_2") (pintype "unspecified"))
      (node (ref "U4") (pin "25") (pinfunction "IO0_25") (pintype "unspecified"))
    )
    (net (code "48") (name "GPIO0_STRAP") (class "Default")
      (node (ref "C12") (pin "2") (pinfunction "2_2") (pintype "unspecified"))
      (node (ref "R9") (pin "1") (pinfunction "1_1") (pintype "input"))
      (node (ref "SW2") (pin "1") (pinfunction "A_1") (pintype "unspecified"))
    )
    (net (code "49") (name "GPIO4") (class "Default")
      (node (ref "H3") (pin "3") (pinfunction "3_3") (pintype "unspecified"))
      (node (ref "U4") (pin "26") (pinfunction "IO4_26") (pintype "unspecified"))
    )
    (net (code "50") (name "GPIO5") (class "Default")
      (node (ref "H3") (pin "1") (pinfunction "1_1") (pintype "unspecified"))
      (node (ref "U4") (pin "29") (pinfunction "IO5_29") (pintype "unspecified"))
    )
    (net (code "51") (name "GPIO23") (class "Default")
      (node (ref "H3") (pin "2") (pinfunction "2_2") (pintype "unspecified"))
      (node (ref "U4") (pin "37") (pinfunction "IO23_37") (pintype "unspecified"))
    )
    (net (code "52") (name "INTA_0") (class "Default")
      (node (ref "U4") (pin "9") (pinfunction "IO33_9") (pintype "unspecified"))
      (node (ref "U7") (pin "20") (pinfunction "INTA_20") (pintype "unspecified"))
    )
    (net (code "53") (name "INTA_1") (class "Default")
      (node (ref "U4") (pin "11") (pinfunction "IO26_11") (pintype "unspecified"))
      (node (ref "U8") (pin "20") (pinfunction "INTA_20") (pintype "unspecified"))
    )
    (net (code "54") (name "INTB_0") (class "Default")
      (node (ref "U4") (pin "10") (pinfunction "IO25_10") (pintype "unspecified"))
      (node (ref "U7") (pin "19") (pinfunction "INTB_19") (pintype "unspecified"))
    )
    (net (code "55") (name "INTB_1") (class "Default")
      (node (ref "U4") (pin "12") (pinfunction "IO27_12") (pintype "unspecified"))
      (node (ref "U8") (pin "19") (pinfunction "INTB_19") (pintype "unspecified"))
    )
    (net (code "56") (name "IO1") (class "Default")
      (node (ref "H1") (pin "1") (pinfunction "1_1") (pintype "unspecified"))
      (node (ref "U8") (pin "4") (pinfunction "GPB3_4") (pintype "bidirectional"))
    )
    (net (code "57") (name "IO2") (class "Default")
      (node (ref "H1") (pin "2") (pinfunction "2_2") (pintype "unspecified"))
      (node (ref "U8") (pin "5") (pinfunction "GPB4_5") (pintype "bidirectional"))
    )
    (net (code "58") (name "IO3") (class "Default")
      (node (ref "H1") (pin "3") (pinfunction "3_3") (pintype "unspecified"))
      (node (ref "U8") (pin "6") (pinfunction "GPB5_6") (pintype "bidirectional"))
    )
    (net (code "59") (name "IO4") (class "Default")
      (node (ref "H1") (pin "4") (pinfunction "4_4") (pintype "unspecified"))
      (node (ref "U8") (pin "7") (pinfunction "GPB6_7") (pintype "bidirectional"))
    )
    (net (code "60") (name "IO5") (class "Default")
      (node (ref "H1") (pin "5") (pinfunction "5_5") (pintype "unspecified"))
      (node (ref "U8") (pin "8") (pinfunction "GPB7_8") (pintype "bidirectional"))
    )
    (net (code "61") (name "IO6") (class "Default")
      (node (ref "H1") (pin "6") (pinfunction "6_6") (pintype "unspecified"))
      (node (ref "U8") (pin "27") (pinfunction "GPA6_27") (pintype "bidirectional"))
    )
    (net (code "62") (name "IO7") (class "Default")
      (node (ref "H1") (pin "7") (pinfunction "7_7") (pintype "unspecified"))
      (node (ref "U8") (pin "28") (pinfunction "GPA7_28") (pintype "bidirectional"))
    )
    (net (code "63") (name "IO8") (class "Default")
      (node (ref "H2") (pin "1") (pinfunction "1_1") (pintype "unspecified"))
      (node (ref "U9") (pin "3") (pinfunction "GPB2_3") (pintype "bidirectional"))
    )
    (net (code "64") (name "IO9") (class "Default")
      (node (ref "H2") (pin "2") (pinfunction "2_2") (pintype "unspecified"))
      (node (ref "U9") (pin "4") (pinfunction "GPB3_4") (pintype "bidirectional"))
    )
    (net (code "65") (name "IO10") (class "Default")
      (node (ref "H2") (pin "3") (pinfunction "3_3") (pintype "unspecified"))
      (node (ref "U9") (pin "5") (pinfunction "GPB4_5") (pintype "bidirectional"))
    )
    (net (code "66") (name "IO11") (class "Default")
      (node (ref "H2") (pin "4") (pinfunction "4_4") (pintype "unspecified"))
      (node (ref "U9") (pin "6") (pinfunction "GPB5_6") (pintype "bidirectional"))
    )
    (net (code "67") (name "IO12") (class "Default")
      (node (ref "H2") (pin "5") (pinfunction "5_5") (pintype "unspecified"))
      (node (ref "U9") (pin "7") (pinfunction "GPB6_7") (pintype "bidirectional"))
    )
    (net (code "68") (name "IO13") (class "Default")
      (node (ref "H2") (pin "6") (pinfunction "6_6") (pintype "unspecified"))
      (node (ref "U9") (pin "8") (pinfunction "GPB7_8") (pintype "bidirectional"))
    )
    (net (code "69") (name "Joystick_X") (class "Default")
      (node (ref "C1") (pin "21") (pinfunction "21_21") (pintype "unspecified"))
      (node (ref "R38") (pin "2") (pinfunction "2_2") (pintype "input"))
    )
    (net (code "70") (name "Joystick_X_3.3") (class "Default")
      (node (ref "C19") (pin "2") (pinfunction "2_2") (pintype "unspecified"))
      (node (ref "R38") (pin "1") (pinfunction "1_1") (pintype "input"))
      (node (ref "R44") (pin "2") (pinfunction "2_2") (pintype "input"))
      (node (ref "U4") (pin "6") (pinfunction "IO34_6") (pintype "unspecified"))
    )
    (net (code "71") (name "Joystick_Y") (class "Default")
      (node (ref "C1") (pin "23") (pinfunction "23_23") (pintype "unspecified"))
      (node (ref "R39") (pin "2") (pinfunction "2_2") (pintype "input"))
    )
    (net (code "72") (name "Joystick_Y_3.3") (class "Default")
      (node (ref "C20") (pin "2") (pinfunction "2_2") (pintype "unspecified"))
      (node (ref "R39") (pin "1") (pinfunction "1_1") (pintype "input"))
      (node (ref "R45") (pin "2") (pinfunction "2_2") (pintype "input"))
      (node (ref "U4") (pin "5") (pinfunction "SENSOR_VN_5") (pintype "unspecified"))
    )
    (net (code "73") (name "Joystick_Z") (class "Default")
      (node (ref "C1") (pin "25") (pinfunction "25_25") (pintype "unspecified"))
      (node (ref "R40") (pin "2") (pinfunction "2_2") (pintype "input"))
    )
    (net (code "74") (name "Joystick_Z_3.3") (class "Default")
      (node (ref "C21") (pin "2") (pinfunction "2_2") (pintype "unspecified"))
      (node (ref "R40") (pin "1") (pinfunction "1_1") (pintype "input"))
      (node (ref "R46") (pin "2") (pinfunction "2_2") (pintype "input"))
      (node (ref "U4") (pin "4") (pinfunction "SENSOR_VP_4") (pintype "unspecified"))
    )
    (net (code "75") (name "LED_IO2") (class "Default")
      (node (ref "R4") (pin "1") (pinfunction "1_1") (pintype "input"))
      (node (ref "R6") (pin "1") (pinfunction "1_1") (pintype "input"))
      (node (ref "U4") (pin "24") (pinfunction "IO2_24") (pintype "unspecified"))
    )
    (net (code "76") (name "Motor_Start") (class "Default")
      (node (ref "C1") (pin "11") (pinfunction "11_11") (pintype "unspecified"))
      (node (ref "R54") (pin "2") (pinfunction "2_2") (pintype "input"))
      (node (ref "U8") (pin "1") (pinfunction "GPB0_1") (pintype "bidirectional"))
    )
    (net (code "77") (name "Net-(D1-A)") (class "Default")
      (node (ref "C1") (pin "31") (pinfunction "31_31") (pintype "unspecified"))
      (node (ref "C3") (pin "1") (pinfunction "1_1") (pintype "input"))
      (node (ref "C4") (pin "1") (pinfunction "1_1") (pintype "input"))
      (node (ref "CN1") (pin "2") (pinfunction "2_2") (pintype "unspecified"))
      (node (ref "D1") (pin "2") (pinfunction "A_2") (pintype "unspecified"))
    )
    (net (code "78") (name "Net-(LED1-A)") (class "Default")
      (node (ref "LED1") (pin "1") (pinfunction "A_1") (pintype "input"))
      (node (ref "R2") (pin "2") (pinfunction "2_2") (pintype "input"))
    )
    (net (code "79") (name "Net-(LED2-A)") (class "Default")
      (node (ref "LED2") (pin "2") (pinfunction "A_2") (pintype "input"))
      (node (ref "R4") (pin "2") (pinfunction "2_2") (pintype "input"))
    )
    (net (code "80") (name "Net-(Q1-B)") (class "Default")
      (node (ref "Q1") (pin "1") (pinfunction "B_1") (pintype "unspecified"))
      (node (ref "R13") (pin "2") (pinfunction "2_2") (pintype "input"))
    )
    (net (code "81") (name "Net-(Q2-B)") (class "Default")
      (node (ref "Q2") (pin "1") (pinfunction "B_1") (pintype "unspecified"))
      (node (ref "R14") (pin "2") (pinfunction "2_2") (pintype "input"))
    )
    (net (code "82") (name "Net-(U3-RSTb)") (class "Default")
      (node (ref "R10") (pin "2") (pinfunction "2_2") (pintype "input"))
      (node (ref "U3") (pin "9") (pinfunction "RSTb_9") (pintype "unspecified"))
    )
    (net (code "83") (name "Net-(U3-SUSPENDb)") (class "Default")
      (node (ref "R11") (pin "1") (pinfunction "1_1") (pintype "input"))
      (node (ref "U3") (pin "15") (pinfunction "SUSPENDb_15") (pintype "unspecified"))
    )
    (net (code "84") (name "Net-(U3-VBUS)") (class "Default")
      (node (ref "R5") (pin "2") (pinfunction "2_2") (pintype "input"))
      (node (ref "R7") (pin "2") (pinfunction "2_2") (pintype "unspecified"))
      (node (ref "U3") (pin "8") (pinfunction "VBUS_8") (pintype "unspecified"))
    )
    (net (code "85") (name "Net-(U3-VIO)") (class "Default")
      (node (ref "R3") (pin "1") (pinfunction "1_1") (pintype "input"))
      (node (ref "U3") (pin "5") (pinfunction "VIO_5") (pintype "unspecified"))
    )
    (net (code "86") (name "OCS2_SCL") (class "Default")
      (node (ref "C1") (pin "8") (pinfunction "8_8") (pintype "unspecified"))
      (node (ref "U4") (pin "31") (pinfunction "IO19_31") (pintype "unspecified"))
    )
    (net (code "87") (name "OCS2_SDA") (class "Default")
      (node (ref "C1") (pin "6") (pinfunction "6_6") (pintype "unspecified"))
      (node (ref "U4") (pin "30") (pinfunction "IO18_30") (pintype "unspecified"))
    )
    (net (code "88") (name "OK") (class "Default")
      (node (ref "C1") (pin "15") (pinfunction "15_15") (pintype "unspecified"))
      (node (ref "R56") (pin "2") (pinfunction "2_2") (pintype "input"))
      (node (ref "U8") (pin "3") (pinfunction "GPB2_3") (pintype "bidirectional"))
    )
    (net (code "89") (name "Programm_Start") (class "Default")
      (node (ref "C1") (pin "13") (pinfunction "13_13") (pintype "unspecified"))
      (node (ref "R55") (pin "2") (pinfunction "2_2") (pintype "input"))
      (node (ref "U8") (pin "2") (pinfunction "GPB1_2") (pintype "bidirectional"))
    )
    (net (code "90") (name "RTS") (class "Default")
      (node (ref "Q1") (pin "2") (pinfunction "E_2") (pintype "unspecified"))
      (node (ref "R14") (pin "1") (pinfunction "1_1") (pintype "input"))
      (node (ref "U3") (pin "19") (pinfunction "RTS_19") (pintype "unspecified"))
    )
    (net (code "91") (name "RXD") (class "Default")
      (node (ref "R8") (pin "2") (pinfunction "2_2") (pintype "input"))
      (node (ref "U3") (pin "20") (pinfunction "RXD_20") (pintype "unspecified"))
    )
    (net (code "92") (name "RXDO") (class "Default")
      (node (ref "R12") (pin "1") (pinfunction "1_1") (pintype "input"))
      (node (ref "U4") (pin "34") (pinfunction "RXD0_34") (pintype "unspecified"))
    )
    (net (code "93") (name "Rotation_Speed") (class "Default")
      (node (ref "C1") (pin "19") (pinfunction "19_19") (pintype "unspecified"))
      (node (ref "R42") (pin "2") (pinfunction "2_2") (pintype "input"))
    )
    (net (code "94") (name "Rotation_Speed_3.3") (class "Default")
      (node (ref "C23") (pin "2") (pinfunction "2_2") (pintype "unspecified"))
      (node (ref "R42") (pin "1") (pinfunction "1_1") (pintype "input"))
      (node (ref "R48") (pin "2") (pinfunction "2_2") (pintype "input"))
      (node (ref "U4") (pin "7") (pinfunction "IO35_7") (pintype "unspecified"))
    )
    (net (code "95") (name "SCL") (class "Default")
      (node (ref "R22") (pin "1") (pinfunction "1_1") (pintype "input"))
      (node (ref "U4") (pin "36") (pinfunction "IO22_36") (pintype "unspecified"))
    )
    (net (code "96") (name "SDA") (class "Default")
      (node (ref "R21") (pin "1") (pinfunction "1_1") (pintype "input"))
      (node (ref "U4") (pin "33") (pinfunction "IO21_33") (pintype "unspecified"))
    )
    (net (code "97") (name "SPI_CLK") (class "Default")
      (node (ref "U6") (pin "20") (pinfunction "B1_20") (pintype "unspecified"))
      (node (ref "U7") (pin "12") (pinfunction "SCK_12") (pintype "unspecified"))
      (node (ref "U8") (pin "12") (pinfunction "SCK_12") (pintype "unspecified"))
      (node (ref "U9") (pin "12") (pinfunction "SCK_12") (pintype "unspecified"))
    )
    (net (code "98") (name "SPI_CLK_3.3") (class "Default")
      (node (ref "U4") (pin "13") (pinfunction "IO14_13") (pintype "unspecified"))
      (node (ref "U6") (pin "1") (pinfunction "A1_1") (pintype "unspecified"))
    )
    (net (code "99") (name "SPI_CS") (class "Default")
      (node (ref "U6") (pin "16") (pinfunction "B4_16") (pintype "unspecified"))
      (node (ref "U7") (pin "11") (pinfunction "CS#_11") (pintype "unspecified"))
      (node (ref "U8") (pin "11") (pinfunction "CS#_11") (pintype "unspecified"))
      (node (ref "U9") (pin "11") (pinfunction "CS#_11") (pintype "unspecified"))
    )
    (net (code "100") (name "SPI_CS_3.3") (class "Default")
      (node (ref "U4") (pin "23") (pinfunction "IO15_23") (pintype "unspecified"))
      (node (ref "U6") (pin "5") (pinfunction "A4_5") (pintype "unspecified"))
    )
    (net (code "101") (name "SPI_MISO") (class "Default")
      (node (ref "U6") (pin "18") (pinfunction "B2_18") (pintype "unspecified"))
      (node (ref "U7") (pin "14") (pinfunction "SO_14") (pintype "unspecified"))
      (node (ref "U8") (pin "14") (pinfunction "SO_14") (pintype "unspecified"))
      (node (ref "U9") (pin "14") (pinfunction "SO_14") (pintype "unspecified"))
    )
    (net (code "102") (name "SPI_MISO_3.3") (class "Default")
      (node (ref "U4") (pin "14") (pinfunction "IO12_14") (pintype "unspecified"))
      (node (ref "U6") (pin "3") (pinfunction "A2_3") (pintype "unspecified"))
    )
    (net (code "103") (name "SPI_MOSI") (class "Default")
      (node (ref "U6") (pin "17") (pinfunction "B3_17") (pintype "unspecified"))
      (node (ref "U7") (pin "13") (pinfunction "SI_13") (pintype "unspecified"))
      (node (ref "U8") (pin "13") (pinfunction "SI_13") (pintype "unspecified"))
      (node (ref "U9") (pin "13") (pinfunction "SI_13") (pintype "unspecified"))
    )
    (net (code "104") (name "SPI_MOSI_3.3") (class "Default")
      (node (ref "U4") (pin "16") (pinfunction "IO13_16") (pintype "unspecified"))
      (node (ref "U6") (pin "4") (pinfunction "A3_4") (pintype "unspecified"))
    )
    (net (code "105") (name "SS_RX_Mesa") (class "Default")
      (node (ref "LPT1_1") (pin "23") (pinfunction "23_23") (pintype "unspecified"))
      (node (ref "R19") (pin "2") (pinfunction "2_2") (pintype "input"))
      (node (ref "U5") (pin "5") (pinfunction "A1_5") (pintype "unspecified"))
    )
    (net (code "106") (name "SS_RX_Mesa_3.3") (class "Default")
      (node (ref "R18") (pin "2") (pinfunction "2_2") (pintype "input"))
      (node (ref "R19") (pin "1") (pinfunction "1_1") (pintype "input"))
      (node (ref "U5") (pin "8") (pinfunction "B1_8") (pintype "unspecified"))
    )
    (net (code "107") (name "SS_TX_Mesa") (class "Default")
      (node (ref "LPT1_1") (pin "25") (pinfunction "25_25") (pintype "unspecified"))
      (node (ref "R20") (pin "2") (pinfunction "2_2") (pintype "input"))
      (node (ref "U5") (pin "4") (pinfunction "A2_4") (pintype "unspecified"))
    )
    (net (code "108") (name "SS_TX_Mesa_3.3") (class "Default")
      (node (ref "R17") (pin "2") (pinfunction "2_2") (pintype "input"))
      (node (ref "R20") (pin "1") (pinfunction "1_1") (pintype "input"))
      (node (ref "U5") (pin "1") (pinfunction "B2_1") (pintype "unspecified"))
    )
    (net (code "109") (name "STEP_A") (class "Default")
      (node (ref "C1") (pin "22") (pinfunction "22_22") (pintype "unspecified"))
      (node (ref "LPT1_1") (pin "15") (pinfunction "15_15") (pintype "unspecified"))
    )
    (net (code "110") (name "STEP_B") (class "Default")
      (node (ref "C1") (pin "26") (pinfunction "26_26") (pintype "unspecified"))
      (node (ref "LPT1_1") (pin "19") (pinfunction "19_19") (pintype "unspecified"))
    )
    (net (code "111") (name "STEP_C") (class "Default")
      (node (ref "C1") (pin "30") (pinfunction "30_30") (pintype "unspecified"))
      (node (ref "LPT1_1") (pin "4") (pinfunction "4_4") (pintype "unspecified"))
    )
    (net (code "112") (name "STEP_X") (class "Default")
      (node (ref "C1") (pin "10") (pinfunction "10_10") (pintype "unspecified"))
      (node (ref "LPT1_1") (pin "3") (pinfunction "3_3") (pintype "unspecified"))
    )
    (net (code "113") (name "STEP_Y") (class "Default")
      (node (ref "C1") (pin "14") (pinfunction "14_14") (pintype "unspecified"))
      (node (ref "LPT1_1") (pin "7") (pinfunction "7_7") (pintype "unspecified"))
    )
    (net (code "114") (name "STEP_Z") (class "Default")
      (node (ref "C1") (pin "18") (pinfunction "18_18") (pintype "unspecified"))
      (node (ref "LPT1_1") (pin "11") (pinfunction "11_11") (pintype "unspecified"))
    )
    (net (code "115") (name "Speed_1") (class "Default")
      (node (ref "C2") (pin "6") (pinfunction "6_6") (pintype "unspecified"))
      (node (ref "R50") (pin "2") (pinfunction "2_2") (pintype "input"))
      (node (ref "U8") (pin "24") (pinfunction "GPA3_24") (pintype "bidirectional"))
    )
    (net (code "116") (name "Speed_2") (class "Default")
      (node (ref "C2") (pin "8") (pinfunction "8_8") (pintype "unspecified"))
      (node (ref "R52") (pin "2") (pinfunction "2_2") (pintype "input"))
      (node (ref "U8") (pin "26") (pinfunction "GPA5_26") (pintype "bidirectional"))
    )
    (net (code "117") (name "Spindel_on{slash}off") (class "Default")
      (node (ref "C1") (pin "5") (pinfunction "5_5") (pintype "unspecified"))
      (node (ref "U9") (pin "1") (pinfunction "GPB0_1") (pintype "bidirectional"))
    )
    (net (code "118") (name "Spindel_pwm") (class "Default")
      (node (ref "C1") (pin "3") (pinfunction "3_3") (pintype "unspecified"))
      (node (ref "LPT1_1") (pin "1") (pinfunction "1_1") (pintype "unspecified"))
    )
    (net (code "119") (name "TXD") (class "Default")
      (node (ref "R12") (pin "2") (pinfunction "2_2") (pintype "input"))
      (node (ref "U3") (pin "21") (pinfunction "TXD_21") (pintype "unspecified"))
    )
    (net (code "120") (name "TXDO") (class "Default")
      (node (ref "R8") (pin "1") (pinfunction "1_1") (pintype "input"))
      (node (ref "U4") (pin "35") (pinfunction "TXD0_35") (pintype "unspecified"))
    )
    (net (code "121") (name "USB_DN") (class "Default")
      (node (ref "D4") (pin "1") (pinfunction "1_1") (pintype "unspecified"))
      (node (ref "U3") (pin "4") (pinfunction "D-_4") (pintype "unspecified"))
      (node (ref "USB1") (pin "5") (pinfunction "DN2_5") (pintype "unspecified"))
      (node (ref "USB1") (pin "7") (pinfunction "DN1_7") (pintype "unspecified"))
    )
    (net (code "122") (name "USB_DP") (class "Default")
      (node (ref "D5") (pin "1") (pinfunction "1_1") (pintype "unspecified"))
      (node (ref "U3") (pin "3") (pinfunction "D+_3") (pintype "unspecified"))
      (node (ref "USB1") (pin "6") (pinfunction "DP1_6") (pintype "unspecified"))
      (node (ref "USB1") (pin "8") (pinfunction "DP2_8") (pintype "unspecified"))
    )
    (net (code "123") (name "VBUS") (class "Default")
      (node (ref "D2") (pin "1") (pinfunction "1_1") (pintype "unspecified"))
      (node (ref "D3") (pin "2") (pinfunction "A_2") (pintype "unspecified"))
      (node (ref "R5") (pin "1") (pinfunction "1_1") (pintype "input"))
      (node (ref "USB1") (pin "11") (pinfunction "VBUS_11") (pintype "unspecified"))
      (node (ref "USB1") (pin "2") (pinfunction "VBUS_2") (pintype "unspecified"))
    )
    (net (code "124") (name "unconnected-(C1-Pad1)") (class "Default")
      (node (ref "C1") (pin "1") (pinfunction "1_1") (pintype "unspecified+no_connect"))
    )
    (net (code "125") (name "unconnected-(C1-Pad2)") (class "Default")
      (node (ref "C1") (pin "2") (pinfunction "2_2") (pintype "unspecified+no_connect"))
    )
    (net (code "126") (name "unconnected-(C1-Pad29)") (class "Default")
      (node (ref "C1") (pin "29") (pinfunction "29_29") (pintype "unspecified+no_connect"))
    )
    (net (code "127") (name "unconnected-(C1-Pad33)") (class "Default")
      (node (ref "C1") (pin "33") (pinfunction "33_33") (pintype "unspecified+no_connect"))
    )
    (net (code "128") (name "unconnected-(C1-Pad34)") (class "Default")
      (node (ref "C1") (pin "34") (pinfunction "34_34") (pintype "unspecified+no_connect"))
    )
    (net (code "129") (name "unconnected-(C2-Pad1)") (class "Default")
      (node (ref "C2") (pin "1") (pinfunction "1_1") (pintype "unspecified+no_connect"))
    )
    (net (code "130") (name "unconnected-(C2-Pad2)") (class "Default")
      (node (ref "C2") (pin "2") (pinfunction "2_2") (pintype "unspecified+no_connect"))
    )
    (net (code "131") (name "unconnected-(C2-Pad33)") (class "Default")
      (node (ref "C2") (pin "33") (pinfunction "33_33") (pintype "unspecified+no_connect"))
    )
    (net (code "132") (name "unconnected-(C2-Pad34)") (class "Default")
      (node (ref "C2") (pin "34") (pinfunction "34_34") (pintype "unspecified+no_connect"))
    )
    (net (code "133") (name "unconnected-(H2-Pad7)") (class "Default")
      (node (ref "H2") (pin "7") (pinfunction "7_7") (pintype "unspecified+no_connect"))
    )
    (net (code "134") (name "unconnected-(SW1-B-Pad2)") (class "Default")
      (node (ref "SW1") (pin "2") (pinfunction "B_2") (pintype "unspecified+no_connect"))
    )
    (net (code "135") (name "unconnected-(SW1-D-Pad4)") (class "Default")
      (node (ref "SW1") (pin "4") (pinfunction "D_4") (pintype "unspecified+no_connect"))
    )
    (net (code "136") (name "unconnected-(SW2-B-Pad2)") (class "Default")
      (node (ref "SW2") (pin "2") (pinfunction "B_2") (pintype "unspecified+no_connect"))
    )
    (net (code "137") (name "unconnected-(SW2-D-Pad4)") (class "Default")
      (node (ref "SW2") (pin "4") (pinfunction "D_4") (pintype "unspecified+no_connect"))
    )
    (net (code "138") (name "unconnected-(U3-CTS-Pad18)") (class "Default")
      (node (ref "U3") (pin "18") (pinfunction "CTS_18") (pintype "unspecified+no_connect"))
    )
    (net (code "139") (name "unconnected-(U3-DCD-Pad24)") (class "Default")
      (node (ref "U3") (pin "24") (pinfunction "DCD_24") (pintype "unspecified+no_connect"))
    )
    (net (code "140") (name "unconnected-(U3-DSR-Pad22)") (class "Default")
      (node (ref "U3") (pin "22") (pinfunction "DSR_22") (pintype "unspecified+no_connect"))
    )
    (net (code "141") (name "unconnected-(U3-GPIO.0{slash}TXT-Pad14)") (class "Default")
      (node (ref "U3") (pin "14") (pinfunction "GPIO.0/TXT_14") (pintype "unspecified+no_connect"))
    )
    (net (code "142") (name "unconnected-(U3-GPIO.1{slash}RXT-Pad13)") (class "Default")
      (node (ref "U3") (pin "13") (pinfunction "GPIO.1/RXT_13") (pintype "unspecified+no_connect"))
    )
    (net (code "143") (name "unconnected-(U3-GPIO.2{slash}RS485-Pad12)") (class "Default")
      (node (ref "U3") (pin "12") (pinfunction "GPIO.2/RS485_12") (pintype "unspecified+no_connect"))
    )
    (net (code "144") (name "unconnected-(U3-GPIO.3{slash}WAKEUP-Pad11)") (class "Default")
      (node (ref "U3") (pin "11") (pinfunction "GPIO.3/WAKEUP_11") (pintype "unspecified+no_connect"))
    )
    (net (code "145") (name "unconnected-(U3-NC-Pad10)") (class "Default")
      (node (ref "U3") (pin "10") (pinfunction "NC_10") (pintype "unspecified+no_connect"))
    )
    (net (code "146") (name "unconnected-(U3-NC-Pad16)") (class "Default")
      (node (ref "U3") (pin "16") (pinfunction "NC_16") (pintype "unspecified+no_connect"))
    )
    (net (code "147") (name "unconnected-(U3-RI{slash}CLK-Pad1)") (class "Default")
      (node (ref "U3") (pin "1") (pinfunction "RI/CLK_1") (pintype "unspecified+no_connect"))
    )
    (net (code "148") (name "unconnected-(U3-SUSPEND-Pad17)") (class "Default")
      (node (ref "U3") (pin "17") (pinfunction "SUSPEND_17") (pintype "unspecified+no_connect"))
    )
    (net (code "149") (name "unconnected-(U4-NC-Pad17)") (class "Default")
      (node (ref "U4") (pin "17") (pinfunction "NC_17") (pintype "unspecified+no_connect"))
    )
    (net (code "150") (name "unconnected-(U4-NC-Pad18)") (class "Default")
      (node (ref "U4") (pin "18") (pinfunction "NC_18") (pintype "unspecified+no_connect"))
    )
    (net (code "151") (name "unconnected-(U4-NC-Pad19)") (class "Default")
      (node (ref "U4") (pin "19") (pinfunction "NC_19") (pintype "unspecified+no_connect"))
    )
    (net (code "152") (name "unconnected-(U4-NC-Pad20)") (class "Default")
      (node (ref "U4") (pin "20") (pinfunction "NC_20") (pintype "unspecified+no_connect"))
    )
    (net (code "153") (name "unconnected-(U4-NC-Pad21)") (class "Default")
      (node (ref "U4") (pin "21") (pinfunction "NC_21") (pintype "unspecified+no_connect"))
    )
    (net (code "154") (name "unconnected-(U4-NC-Pad22)") (class "Default")
      (node (ref "U4") (pin "22") (pinfunction "NC_22") (pintype "unspecified+no_connect"))
    )
    (net (code "155") (name "unconnected-(U4-NC-Pad32)") (class "Default")
      (node (ref "U4") (pin "32") (pinfunction "NC_32") (pintype "unspecified+no_connect"))
    )
    (net (code "156") (name "unconnected-(U6-A5-Pad6)") (class "Default")
      (node (ref "U6") (pin "6") (pinfunction "A5_6") (pintype "unspecified+no_connect"))
    )
    (net (code "157") (name "unconnected-(U6-A6-Pad7)") (class "Default")
      (node (ref "U6") (pin "7") (pinfunction "A6_7") (pintype "unspecified+no_connect"))
    )
    (net (code "158") (name "unconnected-(U6-A7-Pad8)") (class "Default")
      (node (ref "U6") (pin "8") (pinfunction "A7_8") (pintype "unspecified+no_connect"))
    )
    (net (code "159") (name "unconnected-(U6-A8-Pad9)") (class "Default")
      (node (ref "U6") (pin "9") (pinfunction "A8_9") (pintype "unspecified+no_connect"))
    )
    (net (code "160") (name "unconnected-(U6-B5-Pad15)") (class "Default")
      (node (ref "U6") (pin "15") (pinfunction "B5_15") (pintype "unspecified+no_connect"))
    )
    (net (code "161") (name "unconnected-(U6-B6-Pad14)") (class "Default")
      (node (ref "U6") (pin "14") (pinfunction "B6_14") (pintype "unspecified+no_connect"))
    )
    (net (code "162") (name "unconnected-(U6-B7-Pad13)") (class "Default")
      (node (ref "U6") (pin "13") (pinfunction "B7_13") (pintype "unspecified+no_connect"))
    )
    (net (code "163") (name "unconnected-(U6-B8-Pad12)") (class "Default")
      (node (ref "U6") (pin "12") (pinfunction "B8_12") (pintype "unspecified+no_connect"))
    )
    (net (code "164") (name "unconnected-(U9-INTA-Pad20)") (class "Default")
      (node (ref "U9") (pin "20") (pinfunction "INTA_20") (pintype "unspecified+no_connect"))
    )
    (net (code "165") (name "unconnected-(U9-INTB-Pad19)") (class "Default")
      (node (ref "U9") (pin "19") (pinfunction "INTB_19") (pintype "unspecified+no_connect"))
    )
    (net (code "166") (name "unconnected-(USB1-CC1-Pad4)") (class "Default")
      (node (ref "USB1") (pin "4") (pinfunction "CC1_4") (pintype "unspecified+no_connect"))
    )
    (net (code "167") (name "unconnected-(USB1-CC2-Pad10)") (class "Default")
      (node (ref "USB1") (pin "10") (pinfunction "CC2_10") (pintype "unspecified+no_connect"))
    )
    (net (code "168") (name "unconnected-(USB1-SBU1-Pad9)") (class "Default")
      (node (ref "USB1") (pin "9") (pinfunction "SBU1_9") (pintype "unspecified+no_connect"))
    )
    (net (code "169") (name "unconnected-(USB1-SBU2-Pad3)") (class "Default")
      (node (ref "USB1") (pin "3") (pinfunction "SBU2_3") (pintype "unspecified+no_connect"))
    )
  )
)
